# PhaseShifter.net
KiCad netlist of a schematic drawn in Altium Designer
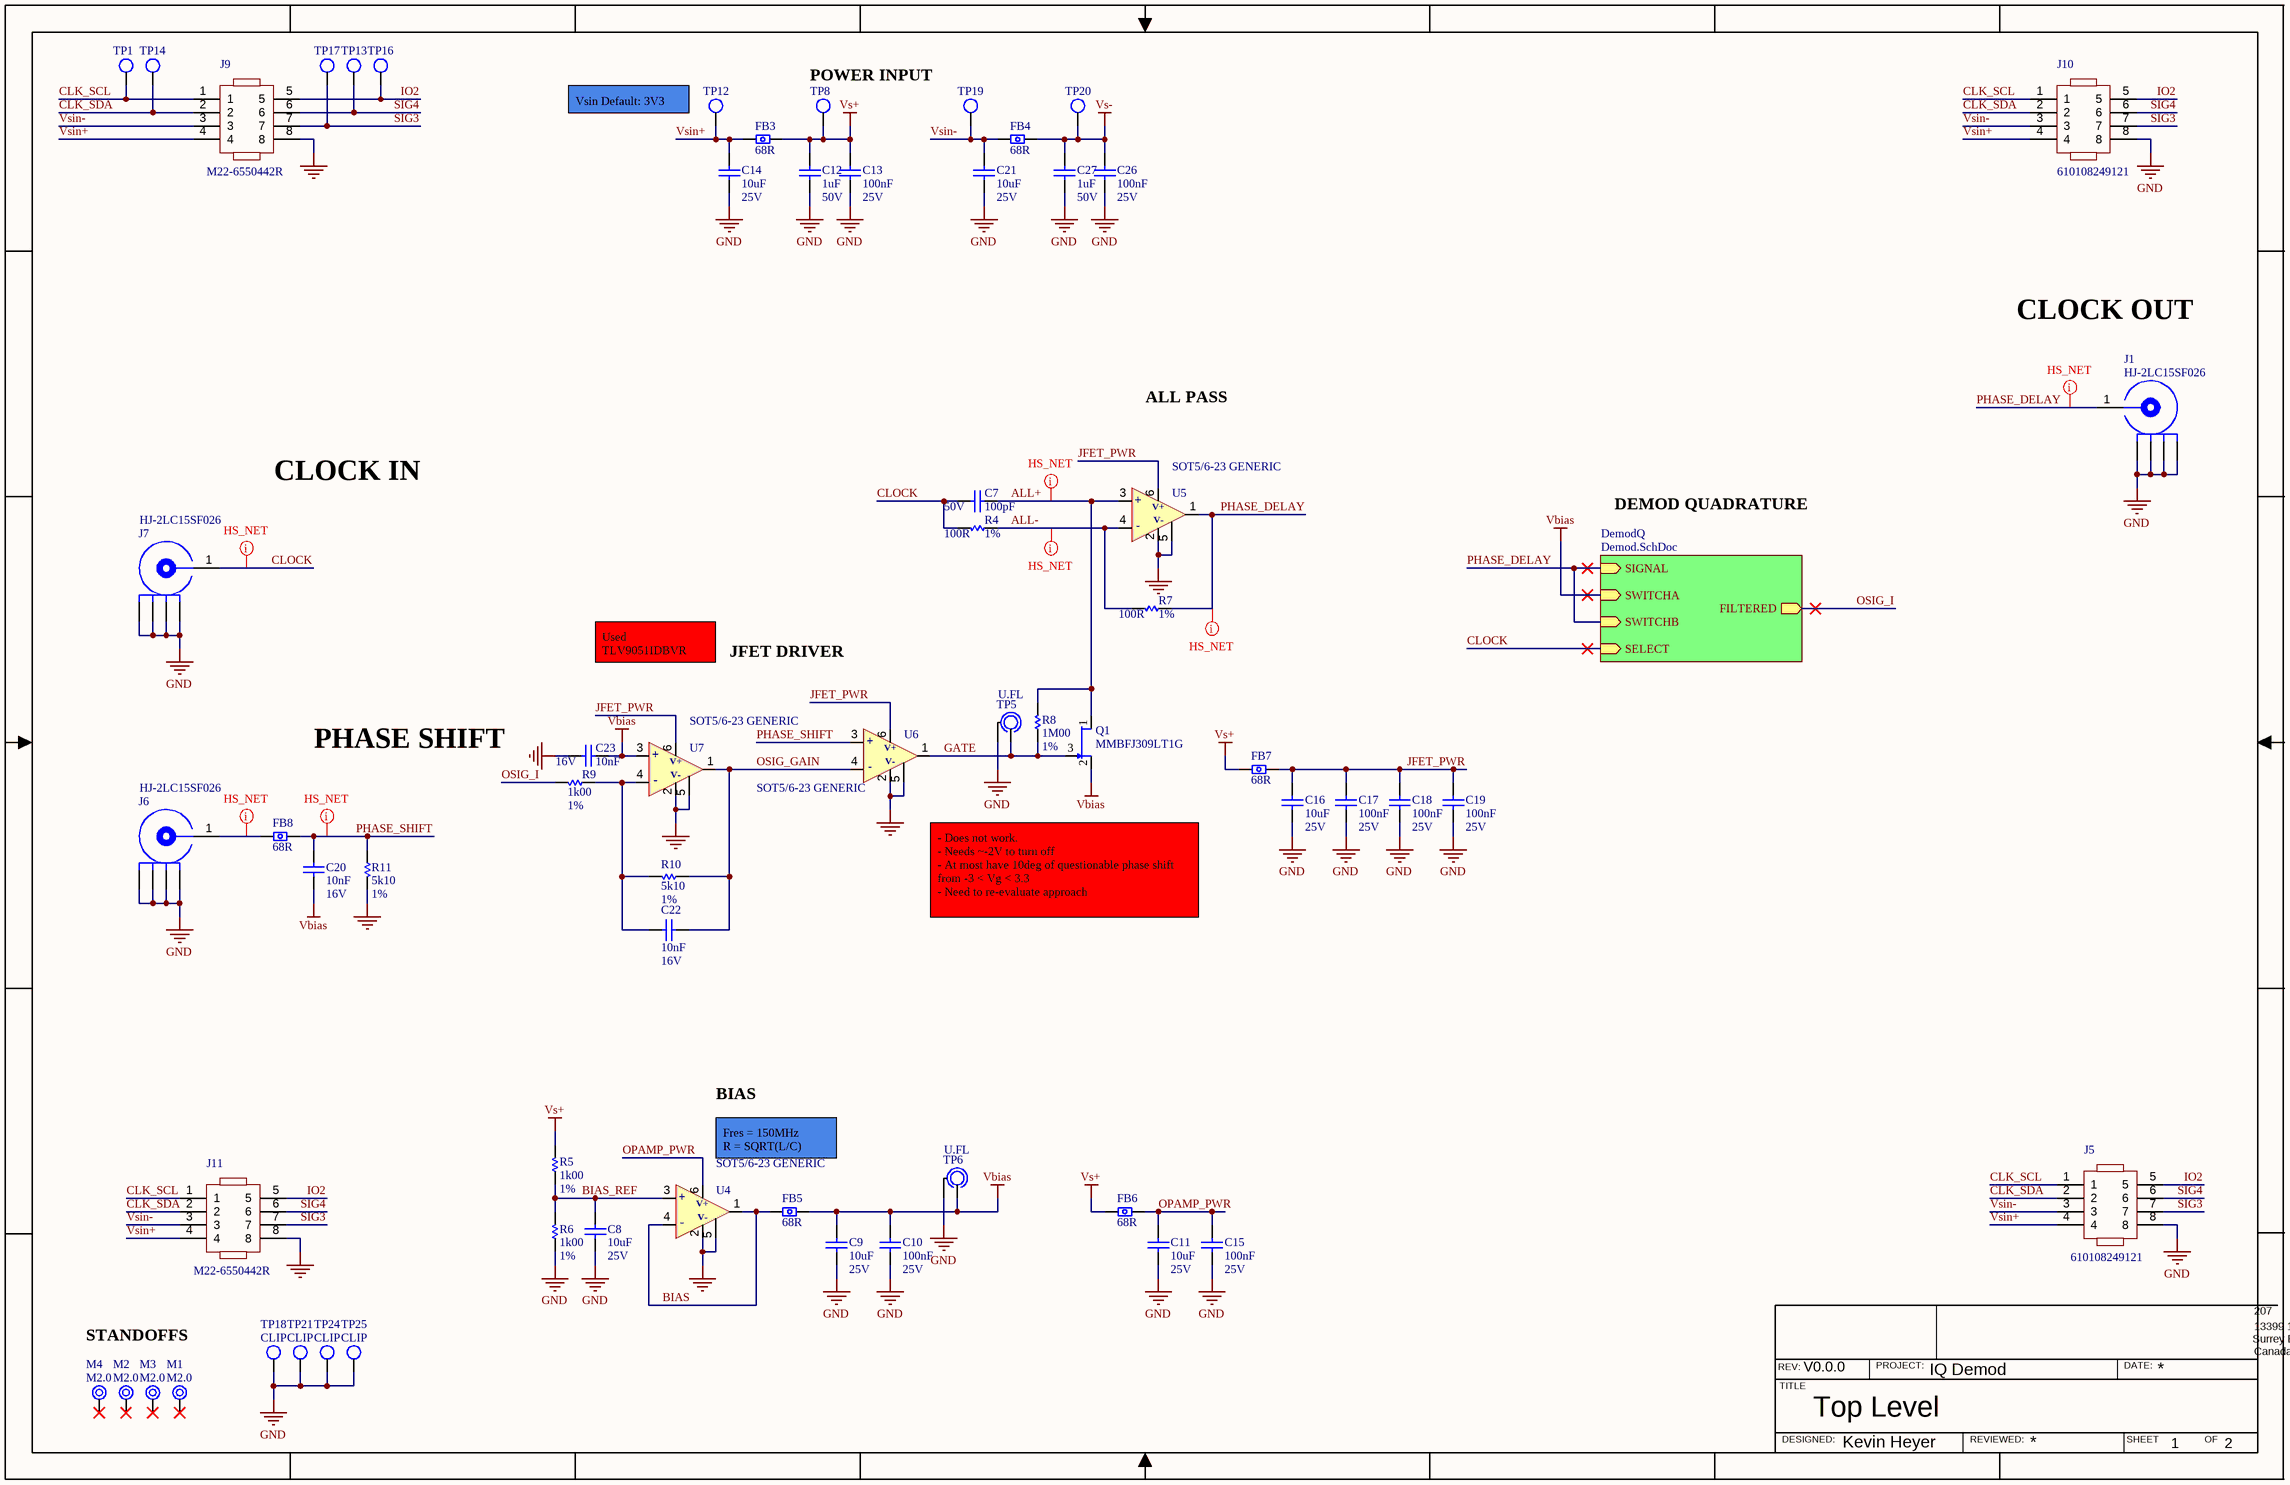
[diagram p0: PhaseShifter.SchDoc]

(export (version "E")
  (design (tool "Eeschema 10.0.6"))
  (components
    (comp (ref "C7")
      (value "100pF")
      (footprint "C0402")
      (description "0402 100 pF 50 V ±5% Tolerance NP0/C0G Multilayer Ceramic Chip Capacitor")
      (fields
        (field (name "MANUFACTURER") "Yageo")
        (field (name "MANUFACTURER PART NUMBER") "CC0402JPNPO9BN101")
        (field (name "VOLTAGE RATING (DC)") "50V")
      )
      (libsource (lib "Symbols") (part "CAP CER 100pF 50V C0G 0402"))
    )
    (comp (ref "C8")
      (value "10uF")
      (footprint "c0805")
      (description "Cap Ceramic 10uF 25V X5R 10% SMD 0805 85°C Embossed T/R")
      (fields
        (field (name "MANUFACTURER") "Samsung")
        (field (name "MANUFACTURER PART NUMBER") "CL21A106KAYNNNE")
        (field (name "VOLTAGE RATING") "25V")
      )
      (libsource (lib "OPAMP_DEV_SOT5_6-23") (part "CAP CER 10uF 25V X5R 0805"))
    )
    (comp (ref "C9")
      (value "10uF")
      (footprint "c0805")
      (description "Cap Ceramic 10uF 25V X5R 10% SMD 0805 85°C Embossed T/R")
      (fields
        (field (name "MANUFACTURER") "Samsung")
        (field (name "MANUFACTURER PART NUMBER") "CL21A106KAYNNNE")
        (field (name "VOLTAGE RATING") "25V")
      )
      (libsource (lib "OPAMP_DEV_SOT5_6-23") (part "CAP CER 10uF 25V X5R 0805"))
    )
    (comp (ref "C10")
      (value "100nF")
      (footprint "C0402")
      (description "Cap Ceramic 0.1uF 25V X5R 10% Pad SMD 0402 85°C T/R / Multi Layer Ceramic Capacitor (MLCC)")
      (fields
        (field (name "MANUFACTURER") "Samsung")
        (field (name "MANUFACTURER PART NUMBER") "CL05A104KA5NNNC")
        (field (name "VOLTAGE RATING") "25V")
      )
      (libsource (lib "OPAMP_DEV_SOT5_6-23") (part "CAP CER 100nF 25V X5R 0402"))
    )
    (comp (ref "C11")
      (value "10uF")
      (footprint "c0805")
      (description "Cap Ceramic 10uF 25V X5R 10% SMD 0805 85°C Embossed T/R")
      (fields
        (field (name "MANUFACTURER") "Samsung")
        (field (name "MANUFACTURER PART NUMBER") "CL21A106KAYNNNE")
        (field (name "VOLTAGE RATING") "25V")
      )
      (libsource (lib "OPAMP_DEV_SOT5_6-23") (part "CAP CER 10uF 25V X5R 0805"))
    )
    (comp (ref "C12")
      (value "1uF")
      (footprint "c0603")
      (description "Multilayer Ceramic Capacitors (High dielectric type), 50V, 1 uF, ± 10 %, 0603, X5R, RoHS")
      (fields
        (field (name "MANUFACTURER") "Taiyo Yuden")
        (field (name "MANUFACTURER PART NUMBER") "UMK107BJ105KA-T")
        (field (name "VOLTAGE RATING") "50V")
      )
      (libsource (lib "OPAMP_DEV_SOT5_6-23") (part "CAP CER 1uF 50V X5R 0603"))
    )
    (comp (ref "C13")
      (value "100nF")
      (footprint "C0402")
      (description "Cap Ceramic 0.1uF 25V X5R 10% Pad SMD 0402 85°C T/R / Multi Layer Ceramic Capacitor (MLCC)")
      (fields
        (field (name "MANUFACTURER") "Samsung")
        (field (name "MANUFACTURER PART NUMBER") "CL05A104KA5NNNC")
        (field (name "VOLTAGE RATING") "25V")
      )
      (libsource (lib "OPAMP_DEV_SOT5_6-23") (part "CAP CER 100nF 25V X5R 0402"))
    )
    (comp (ref "C14")
      (value "10uF")
      (footprint "c0805")
      (description "Cap Ceramic 10uF 25V X5R 10% SMD 0805 85°C Embossed T/R")
      (fields
        (field (name "MANUFACTURER") "Samsung")
        (field (name "MANUFACTURER PART NUMBER") "CL21A106KAYNNNE")
        (field (name "VOLTAGE RATING") "25V")
      )
      (libsource (lib "OPAMP_DEV_SOT5_6-23") (part "CAP CER 10uF 25V X5R 0805"))
    )
    (comp (ref "C15")
      (value "100nF")
      (footprint "C0402")
      (description "Cap Ceramic 0.1uF 25V X5R 10% Pad SMD 0402 85°C T/R / Multi Layer Ceramic Capacitor (MLCC)")
      (fields
        (field (name "MANUFACTURER") "Samsung")
        (field (name "MANUFACTURER PART NUMBER") "CL05A104KA5NNNC")
        (field (name "VOLTAGE RATING") "25V")
      )
      (libsource (lib "OPAMP_DEV_SOT5_6-23") (part "CAP CER 100nF 25V X5R 0402"))
    )
    (comp (ref "C16")
      (value "10uF")
      (footprint "c0805")
      (description "Cap Ceramic 10uF 25V X5R 10% SMD 0805 85°C Embossed T/R")
      (fields
        (field (name "MANUFACTURER") "Samsung")
        (field (name "MANUFACTURER PART NUMBER") "CL21A106KAYNNNE")
        (field (name "VOLTAGE RATING") "25V")
      )
      (libsource (lib "OPAMP_DEV_SOT5_6-23") (part "CAP CER 10uF 25V X5R 0805"))
    )
    (comp (ref "C17")
      (value "100nF")
      (footprint "C0402")
      (description "Cap Ceramic 0.1uF 25V X5R 10% Pad SMD 0402 85°C T/R / Multi Layer Ceramic Capacitor (MLCC)")
      (fields
        (field (name "MANUFACTURER") "Samsung")
        (field (name "MANUFACTURER PART NUMBER") "CL05A104KA5NNNC")
        (field (name "VOLTAGE RATING") "25V")
      )
      (libsource (lib "OPAMP_DEV_SOT5_6-23") (part "CAP CER 100nF 25V X5R 0402"))
    )
    (comp (ref "C18")
      (value "100nF")
      (footprint "C0402")
      (description "Cap Ceramic 0.1uF 25V X5R 10% Pad SMD 0402 85°C T/R / Multi Layer Ceramic Capacitor (MLCC)")
      (fields
        (field (name "MANUFACTURER") "Samsung")
        (field (name "MANUFACTURER PART NUMBER") "CL05A104KA5NNNC")
        (field (name "VOLTAGE RATING") "25V")
      )
      (libsource (lib "OPAMP_DEV_SOT5_6-23") (part "CAP CER 100nF 25V X5R 0402"))
    )
    (comp (ref "C19")
      (value "100nF")
      (footprint "C0402")
      (description "Cap Ceramic 0.1uF 25V X5R 10% Pad SMD 0402 85°C T/R / Multi Layer Ceramic Capacitor (MLCC)")
      (fields
        (field (name "MANUFACTURER") "Samsung")
        (field (name "MANUFACTURER PART NUMBER") "CL05A104KA5NNNC")
        (field (name "VOLTAGE RATING") "25V")
      )
      (libsource (lib "OPAMP_DEV_SOT5_6-23") (part "CAP CER 100nF 25V X5R 0402"))
    )
    (comp (ref "C20")
      (value "10nF")
      (footprint "c0402")
      (description "0402 10 nF 16 V -20 / +80 % Tolerance Y5V SMT Multilayer Ceramic Capacitor")
      (fields
        (field (name "MANUFACTURER") "Yageo")
        (field (name "MANUFACTURER PART NUMBER") "CC0402ZRY5V7BB103")
        (field (name "VOLTAGE RATING") "16V")
      )
      (libsource (lib "Symbols") (part "CAP CER 10nF 16V Y5V 0402"))
    )
    (comp (ref "C21")
      (value "10uF")
      (footprint "c0805")
      (description "Cap Ceramic 10uF 25V X5R 10% SMD 0805 85°C Embossed T/R")
      (fields
        (field (name "MANUFACTURER") "Samsung")
        (field (name "MANUFACTURER PART NUMBER") "CL21A106KAYNNNE")
        (field (name "VOLTAGE RATING") "25V")
      )
      (libsource (lib "OPAMP_DEV_SOT5_6-23") (part "CAP CER 10uF 25V X5R 0805"))
    )
    (comp (ref "C22")
      (value "10nF")
      (footprint "c0402")
      (description "0402 10 nF 16 V -20 / +80 % Tolerance Y5V SMT Multilayer Ceramic Capacitor")
      (fields
        (field (name "MANUFACTURER") "Yageo")
        (field (name "MANUFACTURER PART NUMBER") "CC0402ZRY5V7BB103")
        (field (name "VOLTAGE RATING") "16V")
      )
      (libsource (lib "Symbols") (part "CAP CER 10nF 16V Y5V 0402"))
    )
    (comp (ref "C23")
      (value "10nF")
      (footprint "c0402")
      (description "0402 10 nF 16 V -20 / +80 % Tolerance Y5V SMT Multilayer Ceramic Capacitor")
      (fields
        (field (name "MANUFACTURER") "Yageo")
        (field (name "MANUFACTURER PART NUMBER") "CC0402ZRY5V7BB103")
        (field (name "VOLTAGE RATING") "16V")
      )
      (libsource (lib "Symbols") (part "CAP CER 10nF 16V Y5V 0402"))
    )
    (comp (ref "C26")
      (value "100nF")
      (footprint "C0402")
      (description "Cap Ceramic 0.1uF 25V X5R 10% Pad SMD 0402 85°C T/R / Multi Layer Ceramic Capacitor (MLCC)")
      (fields
        (field (name "MANUFACTURER") "Samsung")
        (field (name "MANUFACTURER PART NUMBER") "CL05A104KA5NNNC")
        (field (name "VOLTAGE RATING") "25V")
      )
      (libsource (lib "OPAMP_DEV_SOT5_6-23") (part "CAP CER 100nF 25V X5R 0402"))
    )
    (comp (ref "C27")
      (value "1uF")
      (footprint "c0603")
      (description "Multilayer Ceramic Capacitors (High dielectric type), 50V, 1 uF, ± 10 %, 0603, X5R, RoHS")
      (fields
        (field (name "MANUFACTURER") "Taiyo Yuden")
        (field (name "MANUFACTURER PART NUMBER") "UMK107BJ105KA-T")
        (field (name "VOLTAGE RATING") "50V")
      )
      (libsource (lib "OPAMP_DEV_SOT5_6-23") (part "CAP CER 1uF 50V X5R 0603"))
    )
    (comp (ref "FB3")
      (value "68R")
      (footprint "FB0402")
      (description "Ferrite Beads Multi-Layer 68Ohm 25% 100MHz 400mA 310mOhm DCR 0402 T/R")
      (fields
        (field (name "MANUFACTURER") "Taiyo Yuden")
        (field (name "MANUFACTURER PART NUMBER") "BK1005LL680-T")
      )
      (libsource (lib "MCU") (part "FB 68R 400mA 310mR 0402"))
    )
    (comp (ref "FB4")
      (value "68R")
      (footprint "FB0402")
      (description "Ferrite Beads Multi-Layer 68Ohm 25% 100MHz 400mA 310mOhm DCR 0402 T/R")
      (fields
        (field (name "MANUFACTURER") "Taiyo Yuden")
        (field (name "MANUFACTURER PART NUMBER") "BK1005LL680-T")
      )
      (libsource (lib "MCU") (part "FB 68R 400mA 310mR 0402"))
    )
    (comp (ref "FB5")
      (value "68R")
      (footprint "FB0402")
      (description "Ferrite Beads Multi-Layer 68Ohm 25% 100MHz 400mA 310mOhm DCR 0402 T/R")
      (fields
        (field (name "MANUFACTURER") "Taiyo Yuden")
        (field (name "MANUFACTURER PART NUMBER") "BK1005LL680-T")
      )
      (libsource (lib "MCU") (part "FB 68R 400mA 310mR 0402"))
    )
    (comp (ref "FB6")
      (value "68R")
      (footprint "FB0402")
      (description "Ferrite Beads Multi-Layer 68Ohm 25% 100MHz 400mA 310mOhm DCR 0402 T/R")
      (fields
        (field (name "MANUFACTURER") "Taiyo Yuden")
        (field (name "MANUFACTURER PART NUMBER") "BK1005LL680-T")
      )
      (libsource (lib "MCU") (part "FB 68R 400mA 310mR 0402"))
    )
    (comp (ref "FB7")
      (value "68R")
      (footprint "FB0402")
      (description "Ferrite Beads Multi-Layer 68Ohm 25% 100MHz 400mA 310mOhm DCR 0402 T/R")
      (fields
        (field (name "MANUFACTURER") "Taiyo Yuden")
        (field (name "MANUFACTURER PART NUMBER") "BK1005LL680-T")
      )
      (libsource (lib "MCU") (part "FB 68R 400mA 310mR 0402"))
    )
    (comp (ref "FB8")
      (value "68R")
      (footprint "FB0402")
      (description "Ferrite Beads Multi-Layer 68Ohm 25% 100MHz 400mA 310mOhm DCR 0402 T/R")
      (fields
        (field (name "MANUFACTURER") "Taiyo Yuden")
        (field (name "MANUFACTURER PART NUMBER") "BK1005LL680-T")
      )
      (libsource (lib "MCU") (part "FB 68R 400mA 310mR 0402"))
    )
    (comp (ref "J1")
      (value "HJ-2LC15SF026")
      (footprint "SMA TH BORE")
      (libsource (lib "") (part "CON SMA BORE TH HJ-SMA058_1"))
    )
    (comp (ref "J5")
      (value "610108249121")
      (footprint "CONN HDR 08 MALE RA 2ROW - duplicate")
      (description "SMT Angled Pin Header WR-PHD, Pitch 2.54 mm, Dual Row, 8 pins")
      (fields (field (name "MANUFACTURER") "Wurth Electronics"))
      (libsource (lib "Symbols") (part "CONN HDR 08 MALE RA 2 ROW"))
    )
    (comp (ref "J6")
      (value "HJ-2LC15SF026")
      (footprint "SMA TH BORE")
      (libsource (lib "Symbols") (part "CON SMA BORE TH HJ-SMA058"))
    )
    (comp (ref "J7")
      (value "HJ-2LC15SF026")
      (footprint "SMA TH BORE")
      (libsource (lib "Symbols") (part "CON SMA BORE TH HJ-SMA058"))
    )
    (comp (ref "J9")
      (value "M22-6550442R")
      (footprint "CONN HDR 08 FEMALE RA 2ROW")
      (description "Conn Socket Strip RCP 8 POS 2mm Solder RA SMD T/R")
      (fields (field (name "MANUFACTURER") "Harwin"))
      (libsource (lib "Symbols") (part "CONN HDR 08 FEMALE RA 2 ROW"))
    )
    (comp (ref "J10")
      (value "610108249121")
      (footprint "CONN HDR 08 MALE RA 2ROW - duplicate")
      (description "SMT Angled Pin Header WR-PHD, Pitch 2.54 mm, Dual Row, 8 pins")
      (fields (field (name "MANUFACTURER") "Wurth Electronics"))
      (libsource (lib "Symbols") (part "CONN HDR 08 MALE RA 2 ROW"))
    )
    (comp (ref "J11")
      (value "M22-6550442R")
      (footprint "CONN HDR 08 FEMALE RA 2ROW")
      (description "Conn Socket Strip RCP 8 POS 2mm Solder RA SMD T/R")
      (fields (field (name "MANUFACTURER") "Harwin"))
      (libsource (lib "Symbols") (part "CONN HDR 08 FEMALE RA 2 ROW"))
    )
    (comp (ref "M1")
      (value "M2.0")
      (footprint "MECH M2.0 UNPLATED")
      (libsource (lib "OPAMP_DEV_SOT5_6-23") (part "MECH M2.0 UNPLATED"))
    )
    (comp (ref "M2")
      (value "M2.0")
      (footprint "MECH M2.0 UNPLATED")
      (libsource (lib "OPAMP_DEV_SOT5_6-23") (part "MECH M2.0 UNPLATED"))
    )
    (comp (ref "M3")
      (value "M2.0")
      (footprint "MECH M2.0 UNPLATED")
      (libsource (lib "OPAMP_DEV_SOT5_6-23") (part "MECH M2.0 UNPLATED"))
    )
    (comp (ref "M4")
      (value "M2.0")
      (footprint "MECH M2.0 UNPLATED")
      (libsource (lib "OPAMP_DEV_SOT5_6-23") (part "MECH M2.0 UNPLATED"))
    )
    (comp (ref "Q1")
      (value "MMBFJ309LT1G")
      (footprint "SOT 23-3")
      (description "Transistor; JFET - VHF/UHF Amplifier; 25 VDC; 10 mADC; SOT-23 (TO-236); Pb-Free")
      (libsource (lib "Symbols") (part "TRANS NJFET 25V SOT23-3 MMBFJ309LT1G"))
    )
    (comp (ref "R4")
      (value "100R")
      (footprint "R0402")
      (description "Res General Purpose Thick Film 0402 100 Ohm 1% 1/16W ±100ppm/°C Molded SMD Paper T/R")
      (fields
        (field (name "MANUFACTURER") "Yageo")
        (field (name "MANUFACTURER PART NUMBER") "RC0402FR-07100RL")
        (field (name "TOLERANCE") "1%")
      )
      (libsource (lib "Symbols") (part "RES 100R 63mW 1% 0402"))
    )
    (comp (ref "R5")
      (value "1k00")
      (footprint "R0402")
      (description "1 kOhms ±1% 0.063W, 1/16W Chip Resistor 0402 (1005 Metric) Moisture Resistant Thick Film")
      (fields
        (field (name "MANUFACTURER") "Yageo")
        (field (name "MANUFACTURER PART NUMBER") "RC0402FR-071KL")
        (field (name "TOLERANCE") "1%")
      )
      (libsource (lib "Symbols") (part "RES 1k00 63mW 0402"))
    )
    (comp (ref "R6")
      (value "1k00")
      (footprint "R0402")
      (description "1 kOhms ±1% 0.063W, 1/16W Chip Resistor 0402 (1005 Metric) Moisture Resistant Thick Film")
      (fields
        (field (name "MANUFACTURER") "Yageo")
        (field (name "MANUFACTURER PART NUMBER") "RC0402FR-071KL")
        (field (name "TOLERANCE") "1%")
      )
      (libsource (lib "Symbols") (part "RES 1k00 63mW 0402"))
    )
    (comp (ref "R7")
      (value "100R")
      (footprint "R0402")
      (description "Res General Purpose Thick Film 0402 100 Ohm 1% 1/16W ±100ppm/°C Molded SMD Paper T/R")
      (fields
        (field (name "MANUFACTURER") "Yageo")
        (field (name "MANUFACTURER PART NUMBER") "RC0402FR-07100RL")
        (field (name "TOLERANCE") "1%")
      )
      (libsource (lib "Symbols") (part "RES 100R 63mW 1% 0402"))
    )
    (comp (ref "R8")
      (value "1M00")
      (footprint "r0402")
      (description "贴片电阻 1000000Ω ± 1.00% 0.0625W ± 100ppm/℃ 0402")
      (fields
        (field (name "MANUFACTURER") "Yageo")
        (field (name "MANUFACTURER PART NUMBER") "RC0402FR-071ML")
        (field (name "TOLERANCE") "1%")
      )
      (libsource (lib "Symbols") (part "RES 1M00 1% 63mW 0402"))
    )
    (comp (ref "R9")
      (value "1k00")
      (footprint "R0402")
      (description "1 kOhms ±1% 0.063W, 1/16W Chip Resistor 0402 (1005 Metric) Moisture Resistant Thick Film")
      (fields
        (field (name "MANUFACTURER") "Yageo")
        (field (name "MANUFACTURER PART NUMBER") "RC0402FR-071KL")
        (field (name "TOLERANCE") "1%")
      )
      (libsource (lib "Symbols") (part "RES 1k00 63mW 0402"))
    )
    (comp (ref "R10")
      (value "5k10")
      (footprint "R0402")
      (description "贴片电阻 5100Ω ± 1.00% 0.0625W ± 100ppm/℃ 0402")
      (fields
        (field (name "MANUFACTURER") "Yageo")
        (field (name "MANUFACTURER PART NUMBER") "RC0402FR-075K1L")
        (field (name "TOLERANCE") "1%")
      )
      (libsource (lib "Symbols") (part "RES 5k10"))
    )
    (comp (ref "R11")
      (value "5k10")
      (footprint "R0402")
      (description "贴片电阻 5100Ω ± 1.00% 0.0625W ± 100ppm/℃ 0402")
      (fields
        (field (name "MANUFACTURER") "Yageo")
        (field (name "MANUFACTURER PART NUMBER") "RC0402FR-075K1L")
        (field (name "TOLERANCE") "1%")
      )
      (libsource (lib "Symbols") (part "RES 5k10"))
    )
    (comp (ref "TP1")
      (value "1mm")
      (footprint "TESTPOINT_SMT")
      (description "SMT testpoint")
      (libsource (lib "OPAMP_DEV_SOT5_6-23") (part "TP 1mm"))
    )
    (comp (ref "TP5")
      (value "U.FL")
      (footprint "U.FL")
      (description "CONN U.FL RCPT STR 50 OHM SMD")
      (fields
        (field (name "MANUFACTURER") "Hirose")
        (field (name "MANUFACTURER PART NUMBER") "U.FL-R-SMT-1(80)")
      )
      (libsource (lib "OPAMP_DEV_SOT5_6-23") (part "TP U.FL"))
    )
    (comp (ref "TP6")
      (value "U.FL")
      (footprint "U.FL")
      (description "CONN U.FL RCPT STR 50 OHM SMD")
      (fields
        (field (name "MANUFACTURER") "Hirose")
        (field (name "MANUFACTURER PART NUMBER") "U.FL-R-SMT-1(80)")
      )
      (libsource (lib "OPAMP_DEV_SOT5_6-23") (part "TP U.FL"))
    )
    (comp (ref "TP8")
      (value "1mm")
      (footprint "TESTPOINT_SMT")
      (description "SMT testpoint")
      (libsource (lib "OPAMP_DEV_SOT5_6-23") (part "TP 1mm"))
    )
    (comp (ref "TP12")
      (value "1mm")
      (footprint "TESTPOINT_SMT")
      (description "SMT testpoint")
      (libsource (lib "OPAMP_DEV_SOT5_6-23") (part "TP 1mm"))
    )
    (comp (ref "TP13")
      (value "1mm")
      (footprint "TESTPOINT_SMT")
      (description "SMT testpoint")
      (libsource (lib "OPAMP_DEV_SOT5_6-23") (part "TP 1mm"))
    )
    (comp (ref "TP14")
      (value "1mm")
      (footprint "TESTPOINT_SMT")
      (description "SMT testpoint")
      (libsource (lib "OPAMP_DEV_SOT5_6-23") (part "TP 1mm"))
    )
    (comp (ref "TP16")
      (value "1mm")
      (footprint "TESTPOINT_SMT")
      (description "SMT testpoint")
      (libsource (lib "OPAMP_DEV_SOT5_6-23") (part "TP 1mm"))
    )
    (comp (ref "TP17")
      (value "1mm")
      (footprint "TESTPOINT_SMT")
      (description "SMT testpoint")
      (libsource (lib "OPAMP_DEV_SOT5_6-23") (part "TP 1mm"))
    )
    (comp (ref "TP18")
      (value "CLIP")
      (footprint "TESTPOINT_CLIP_1206")
      (description "Current Sense Resistors - SMD CHIP CHECKER HT=2.0 1206")
      (fields (field (name "MANUFACTURER") "KOA Speer") (field (name "MANUFACTURER PART NUMBER") "RCWCTE"))
      (libsource (lib "Symbols") (part "TP CLIP 1206 RCWCTE"))
    )
    (comp (ref "TP19")
      (value "1mm")
      (footprint "TESTPOINT_SMT")
      (description "SMT testpoint")
      (libsource (lib "OPAMP_DEV_SOT5_6-23") (part "TP 1mm"))
    )
    (comp (ref "TP20")
      (value "1mm")
      (footprint "TESTPOINT_SMT")
      (description "SMT testpoint")
      (libsource (lib "OPAMP_DEV_SOT5_6-23") (part "TP 1mm"))
    )
    (comp (ref "TP21")
      (value "CLIP")
      (footprint "TESTPOINT_CLIP_1206")
      (description "Current Sense Resistors - SMD CHIP CHECKER HT=2.0 1206")
      (fields (field (name "MANUFACTURER") "KOA Speer") (field (name "MANUFACTURER PART NUMBER") "RCWCTE"))
      (libsource (lib "Symbols") (part "TP CLIP 1206 RCWCTE"))
    )
    (comp (ref "TP24")
      (value "CLIP")
      (footprint "TESTPOINT_CLIP_1206")
      (description "Current Sense Resistors - SMD CHIP CHECKER HT=2.0 1206")
      (fields (field (name "MANUFACTURER") "KOA Speer") (field (name "MANUFACTURER PART NUMBER") "RCWCTE"))
      (libsource (lib "Symbols") (part "TP CLIP 1206 RCWCTE"))
    )
    (comp (ref "TP25")
      (value "CLIP")
      (footprint "TESTPOINT_CLIP_1206")
      (description "Current Sense Resistors - SMD CHIP CHECKER HT=2.0 1206")
      (fields (field (name "MANUFACTURER") "KOA Speer") (field (name "MANUFACTURER PART NUMBER") "RCWCTE"))
      (libsource (lib "Symbols") (part "TP CLIP 1206 RCWCTE"))
    )
    (comp (ref "U4")
      (value "SOT5/6-23 GENERIC")
      (footprint "SOT23-5/6_Modified")
      (libsource (lib "LaserDiode_Analog") (part "IC OPAMP SOT5/6-23 GENERIC"))
    )
    (comp (ref "U5")
      (value "SOT5/6-23 GENERIC")
      (footprint "SOT23-5/6_Modified")
      (libsource (lib "LaserDiode_Analog") (part "IC OPAMP SOT5/6-23 GENERIC"))
    )
    (comp (ref "U6")
      (value "SOT5/6-23 GENERIC")
      (footprint "SOT23-5/6_Modified")
      (libsource (lib "LaserDiode_Analog") (part "IC OPAMP SOT5/6-23 GENERIC"))
    )
    (comp (ref "U7")
      (value "SOT5/6-23 GENERIC")
      (footprint "SOT23-5/6_Modified")
      (libsource (lib "LaserDiode_Analog") (part "IC OPAMP SOT5/6-23 GENERIC"))
    )
  )
  (nets
    (net (code "1") (name "/ALL+") (class "Default")
      (node (ref "C7") (pin "1") (pinfunction "1_1") (pintype "passive"))
      (node (ref "Q1") (pin "1") (pinfunction "D_1") (pintype "passive"))
      (node (ref "R8") (pin "2") (pinfunction "2_2") (pintype "passive"))
      (node (ref "U5") (pin "3") (pinfunction "+_3") (pintype "passive"))
    )
    (net (code "2") (name "/ALL-") (class "Default")
      (node (ref "R4") (pin "1") (pinfunction "1_1") (pintype "passive"))
      (node (ref "R7") (pin "2") (pinfunction "2_2") (pintype "passive"))
      (node (ref "U5") (pin "4") (pinfunction "-_4") (pintype "passive"))
    )
    (net (code "3") (name "/BIAS") (class "Default")
      (node (ref "FB5") (pin "2") (pintype "passive"))
      (node (ref "U4") (pin "1") (pinfunction "1_1") (pintype "passive"))
      (node (ref "U4") (pin "4") (pinfunction "-_4") (pintype "passive"))
    )
    (net (code "4") (name "/BIAS_REF") (class "Default")
      (node (ref "C8") (pin "2") (pinfunction "2_2") (pintype "passive"))
      (node (ref "R5") (pin "1") (pinfunction "1_1") (pintype "passive"))
      (node (ref "R6") (pin "2") (pinfunction "2_2") (pintype "passive"))
      (node (ref "U4") (pin "3") (pinfunction "+_3") (pintype "passive"))
    )
    (net (code "5") (name "/CLK_SCL") (class "Default")
      (node (ref "J10") (pin "1") (pinfunction "1_1") (pintype "passive"))
      (node (ref "J11") (pin "1") (pinfunction "1_1") (pintype "passive"))
      (node (ref "J5") (pin "1") (pinfunction "1_1") (pintype "passive"))
      (node (ref "J9") (pin "1") (pinfunction "1_1") (pintype "passive"))
      (node (ref "TP1") (pin "1") (pinfunction "1_1") (pintype "passive"))
    )
    (net (code "6") (name "/CLK_SDA") (class "Default")
      (node (ref "J10") (pin "2") (pinfunction "2_2") (pintype "passive"))
      (node (ref "J11") (pin "2") (pinfunction "2_2") (pintype "passive"))
      (node (ref "J5") (pin "2") (pinfunction "2_2") (pintype "passive"))
      (node (ref "J9") (pin "2") (pinfunction "2_2") (pintype "passive"))
      (node (ref "TP14") (pin "1") (pinfunction "1_1") (pintype "passive"))
    )
    (net (code "7") (name "/CLOCK") (class "Default")
      (node (ref "C7") (pin "2") (pinfunction "2_2") (pintype "passive"))
      (node (ref "J7") (pin "1") (pinfunction "1_1") (pintype "passive"))
      (node (ref "R4") (pin "2") (pinfunction "2_2") (pintype "passive"))
    )
    (net (code "8") (name "/GATE") (class "Default")
      (node (ref "Q1") (pin "3") (pinfunction "G_3") (pintype "passive"))
      (node (ref "R8") (pin "1") (pinfunction "1_1") (pintype "passive"))
      (node (ref "TP5") (pin "1") (pinfunction "1_1") (pintype "passive"))
      (node (ref "U6") (pin "1") (pinfunction "1_1") (pintype "passive"))
    )
    (net (code "9") (name "/IO2") (class "Default")
      (node (ref "J10") (pin "5") (pinfunction "5_5") (pintype "passive"))
      (node (ref "J11") (pin "5") (pinfunction "5_5") (pintype "passive"))
      (node (ref "J5") (pin "5") (pinfunction "5_5") (pintype "passive"))
      (node (ref "J9") (pin "5") (pinfunction "5_5") (pintype "passive"))
      (node (ref "TP16") (pin "1") (pinfunction "1_1") (pintype "passive"))
    )
    (net (code "10") (name "/JFET_PWR") (class "Default")
      (node (ref "C16") (pin "2") (pinfunction "2_2") (pintype "passive"))
      (node (ref "C17") (pin "1") (pinfunction "1_1") (pintype "passive"))
      (node (ref "C18") (pin "1") (pinfunction "1_1") (pintype "passive"))
      (node (ref "C19") (pin "1") (pinfunction "1_1") (pintype "passive"))
      (node (ref "FB7") (pin "1") (pintype "passive"))
      (node (ref "U5") (pin "6") (pinfunction "V+_6") (pintype "passive"))
      (node (ref "U6") (pin "6") (pinfunction "V+_6") (pintype "passive"))
      (node (ref "U7") (pin "6") (pinfunction "V+_6") (pintype "passive"))
    )
    (net (code "11") (name "/OPAMP_PWR") (class "Default")
      (node (ref "C11") (pin "2") (pinfunction "2_2") (pintype "passive"))
      (node (ref "C15") (pin "1") (pinfunction "1_1") (pintype "passive"))
      (node (ref "FB6") (pin "1") (pintype "passive"))
      (node (ref "U4") (pin "6") (pinfunction "V+_6") (pintype "passive"))
    )
    (net (code "12") (name "/OSIG_GAIN") (class "Default")
      (node (ref "C22") (pin "1") (pinfunction "1_1") (pintype "passive"))
      (node (ref "R10") (pin "1") (pinfunction "1_1") (pintype "passive"))
      (node (ref "U6") (pin "4") (pinfunction "-_4") (pintype "passive"))
      (node (ref "U7") (pin "1") (pinfunction "1_1") (pintype "passive"))
    )
    (net (code "13") (name "/OSIG_I") (class "Default")
      (node (ref "R9") (pin "2") (pinfunction "2_2") (pintype "passive"))
    )
    (net (code "14") (name "/PHASE_DELAY") (class "Default")
      (node (ref "J1") (pin "1") (pinfunction "1_1") (pintype "passive"))
      (node (ref "R7") (pin "1") (pinfunction "1_1") (pintype "passive"))
      (node (ref "U5") (pin "1") (pinfunction "1_1") (pintype "passive"))
    )
    (net (code "15") (name "/PHASE_SHIFT") (class "Default")
      (node (ref "C20") (pin "1") (pinfunction "1_1") (pintype "passive"))
      (node (ref "FB8") (pin "1") (pintype "passive"))
      (node (ref "R11") (pin "1") (pinfunction "1_1") (pintype "passive"))
      (node (ref "U6") (pin "3") (pinfunction "+_3") (pintype "passive"))
    )
    (net (code "16") (name "/SIG3") (class "Default")
      (node (ref "J10") (pin "7") (pinfunction "7_7") (pintype "passive"))
      (node (ref "J11") (pin "7") (pinfunction "7_7") (pintype "passive"))
      (node (ref "J5") (pin "7") (pinfunction "7_7") (pintype "passive"))
      (node (ref "J9") (pin "7") (pinfunction "7_7") (pintype "passive"))
      (node (ref "TP17") (pin "1") (pinfunction "1_1") (pintype "passive"))
    )
    (net (code "17") (name "/SIG4") (class "Default")
      (node (ref "J10") (pin "6") (pinfunction "6_6") (pintype "passive"))
      (node (ref "J11") (pin "6") (pinfunction "6_6") (pintype "passive"))
      (node (ref "J5") (pin "6") (pinfunction "6_6") (pintype "passive"))
      (node (ref "J9") (pin "6") (pinfunction "6_6") (pintype "passive"))
      (node (ref "TP13") (pin "1") (pinfunction "1_1") (pintype "passive"))
    )
    (net (code "18") (name "/Vsin+") (class "Default")
      (node (ref "C14") (pin "2") (pinfunction "2_2") (pintype "passive"))
      (node (ref "FB3") (pin "2") (pintype "passive"))
      (node (ref "J10") (pin "4") (pinfunction "4_4") (pintype "passive"))
      (node (ref "J11") (pin "4") (pinfunction "4_4") (pintype "passive"))
      (node (ref "J5") (pin "4") (pinfunction "4_4") (pintype "passive"))
      (node (ref "J9") (pin "4") (pinfunction "4_4") (pintype "passive"))
      (node (ref "TP12") (pin "1") (pinfunction "1_1") (pintype "passive"))
    )
    (net (code "19") (name "/Vsin-") (class "Default")
      (node (ref "C21") (pin "2") (pinfunction "2_2") (pintype "passive"))
      (node (ref "FB4") (pin "2") (pintype "passive"))
      (node (ref "J10") (pin "3") (pinfunction "3_3") (pintype "passive"))
      (node (ref "J11") (pin "3") (pinfunction "3_3") (pintype "passive"))
      (node (ref "J5") (pin "3") (pinfunction "3_3") (pintype "passive"))
      (node (ref "J9") (pin "3") (pinfunction "3_3") (pintype "passive"))
      (node (ref "TP19") (pin "1") (pinfunction "1_1") (pintype "passive"))
    )
    (net (code "20") (name "GND") (class "Default")
      (node (ref "C10") (pin "2") (pinfunction "2_2") (pintype "passive"))
      (node (ref "C11") (pin "1") (pinfunction "1_1") (pintype "passive"))
      (node (ref "C12") (pin "1") (pinfunction "1_1") (pintype "passive"))
      (node (ref "C13") (pin "1") (pinfunction "1_1") (pintype "passive"))
      (node (ref "C14") (pin "1") (pinfunction "1_1") (pintype "passive"))
      (node (ref "C15") (pin "2") (pinfunction "2_2") (pintype "passive"))
      (node (ref "C16") (pin "1") (pinfunction "1_1") (pintype "passive"))
      (node (ref "C17") (pin "2") (pinfunction "2_2") (pintype "passive"))
      (node (ref "C18") (pin "2") (pinfunction "2_2") (pintype "passive"))
      (node (ref "C19") (pin "2") (pinfunction "2_2") (pintype "passive"))
      (node (ref "C21") (pin "1") (pinfunction "1_1") (pintype "passive"))
      (node (ref "C23") (pin "1") (pinfunction "1_1") (pintype "passive"))
      (node (ref "C26") (pin "1") (pinfunction "1_1") (pintype "passive"))
      (node (ref "C27") (pin "1") (pinfunction "1_1") (pintype "passive"))
      (node (ref "C8") (pin "1") (pinfunction "1_1") (pintype "passive"))
      (node (ref "C9") (pin "1") (pinfunction "1_1") (pintype "passive"))
      (node (ref "J1") (pin "0") (pinfunction "2_0") (pintype "passive"))
      (node (ref "J10") (pin "8") (pinfunction "8_8") (pintype "passive"))
      (node (ref "J11") (pin "8") (pinfunction "8_8") (pintype "passive"))
      (node (ref "J5") (pin "8") (pinfunction "8_8") (pintype "passive"))
      (node (ref "J6") (pin "0") (pinfunction "2_0") (pintype "passive"))
      (node (ref "J7") (pin "0") (pinfunction "2_0") (pintype "passive"))
      (node (ref "J9") (pin "8") (pinfunction "8_8") (pintype "passive"))
      (node (ref "R11") (pin "2") (pinfunction "2_2") (pintype "passive"))
      (node (ref "R6") (pin "1") (pinfunction "1_1") (pintype "passive"))
      (node (ref "TP18") (pin "1") (pinfunction "1_1") (pintype "passive"))
      (node (ref "TP21") (pin "1") (pinfunction "1_1") (pintype "passive"))
      (node (ref "TP24") (pin "1") (pinfunction "1_1") (pintype "passive"))
      (node (ref "TP25") (pin "1") (pinfunction "1_1") (pintype "passive"))
      (node (ref "TP5") (pin "0") (pinfunction "0_0") (pintype "passive"))
      (node (ref "TP6") (pin "0") (pinfunction "0_0") (pintype "passive"))
      (node (ref "U4") (pin "2") (pinfunction "V-_2") (pintype "passive"))
      (node (ref "U4") (pin "5") (pinfunction "1_5") (pintype "passive"))
      (node (ref "U5") (pin "2") (pinfunction "V-_2") (pintype "passive"))
      (node (ref "U5") (pin "5") (pinfunction "1_5") (pintype "passive"))
      (node (ref "U6") (pin "2") (pinfunction "V-_2") (pintype "passive"))
      (node (ref "U6") (pin "5") (pinfunction "1_5") (pintype "passive"))
      (node (ref "U7") (pin "2") (pinfunction "V-_2") (pintype "passive"))
      (node (ref "U7") (pin "5") (pinfunction "1_5") (pintype "passive"))
    )
    (net (code "21") (name "Net-(FB8-Pad2)") (class "Default")
      (node (ref "FB8") (pin "2") (pintype "passive"))
      (node (ref "J6") (pin "1") (pinfunction "1_1") (pintype "passive"))
    )
    (net (code "22") (name "Net-(U7--)") (class "Default")
      (node (ref "C22") (pin "2") (pinfunction "2_2") (pintype "passive"))
      (node (ref "R10") (pin "2") (pinfunction "2_2") (pintype "passive"))
      (node (ref "R9") (pin "1") (pinfunction "1_1") (pintype "passive"))
      (node (ref "U7") (pin "4") (pinfunction "-_4") (pintype "passive"))
    )
    (net (code "23") (name "Vbias") (class "Default")
      (node (ref "C10") (pin "1") (pinfunction "1_1") (pintype "passive"))
      (node (ref "C20") (pin "2") (pinfunction "2_2") (pintype "passive"))
      (node (ref "C23") (pin "2") (pinfunction "2_2") (pintype "passive"))
      (node (ref "C9") (pin "2") (pinfunction "2_2") (pintype "passive"))
      (node (ref "FB5") (pin "1") (pintype "passive"))
      (node (ref "Q1") (pin "2") (pinfunction "S_2") (pintype "passive"))
      (node (ref "TP6") (pin "1") (pinfunction "1_1") (pintype "passive"))
      (node (ref "U7") (pin "3") (pinfunction "+_3") (pintype "passive"))
    )
    (net (code "24") (name "Vs+") (class "Default")
      (node (ref "C12") (pin "2") (pinfunction "2_2") (pintype "passive"))
      (node (ref "C13") (pin "2") (pinfunction "2_2") (pintype "passive"))
      (node (ref "FB3") (pin "1") (pintype "passive"))
      (node (ref "FB6") (pin "2") (pintype "passive"))
      (node (ref "FB7") (pin "2") (pintype "passive"))
      (node (ref "R5") (pin "2") (pinfunction "2_2") (pintype "passive"))
      (node (ref "TP8") (pin "1") (pinfunction "1_1") (pintype "passive"))
    )
    (net (code "25") (name "Vs-") (class "Default")
      (node (ref "C26") (pin "2") (pinfunction "2_2") (pintype "passive"))
      (node (ref "C27") (pin "2") (pinfunction "2_2") (pintype "passive"))
      (node (ref "FB4") (pin "1") (pintype "passive"))
      (node (ref "TP20") (pin "1") (pinfunction "1_1") (pintype "passive"))
    )
    (net (code "26") (name "unconnected-(M1-Pad1)") (class "Default")
      (node (ref "M1") (pin "1") (pinfunction "1_1") (pintype "passive+no_connect"))
    )
    (net (code "27") (name "unconnected-(M2-Pad1)") (class "Default")
      (node (ref "M2") (pin "1") (pinfunction "1_1") (pintype "passive+no_connect"))
    )
    (net (code "28") (name "unconnected-(M3-Pad1)") (class "Default")
      (node (ref "M3") (pin "1") (pinfunction "1_1") (pintype "passive+no_connect"))
    )
    (net (code "29") (name "unconnected-(M4-Pad1)") (class "Default")
      (node (ref "M4") (pin "1") (pinfunction "1_1") (pintype "passive+no_connect"))
    )
  )
)
